# DDR4_SODIMM2.net
KiCad netlist of a schematic drawn in Altium Designer
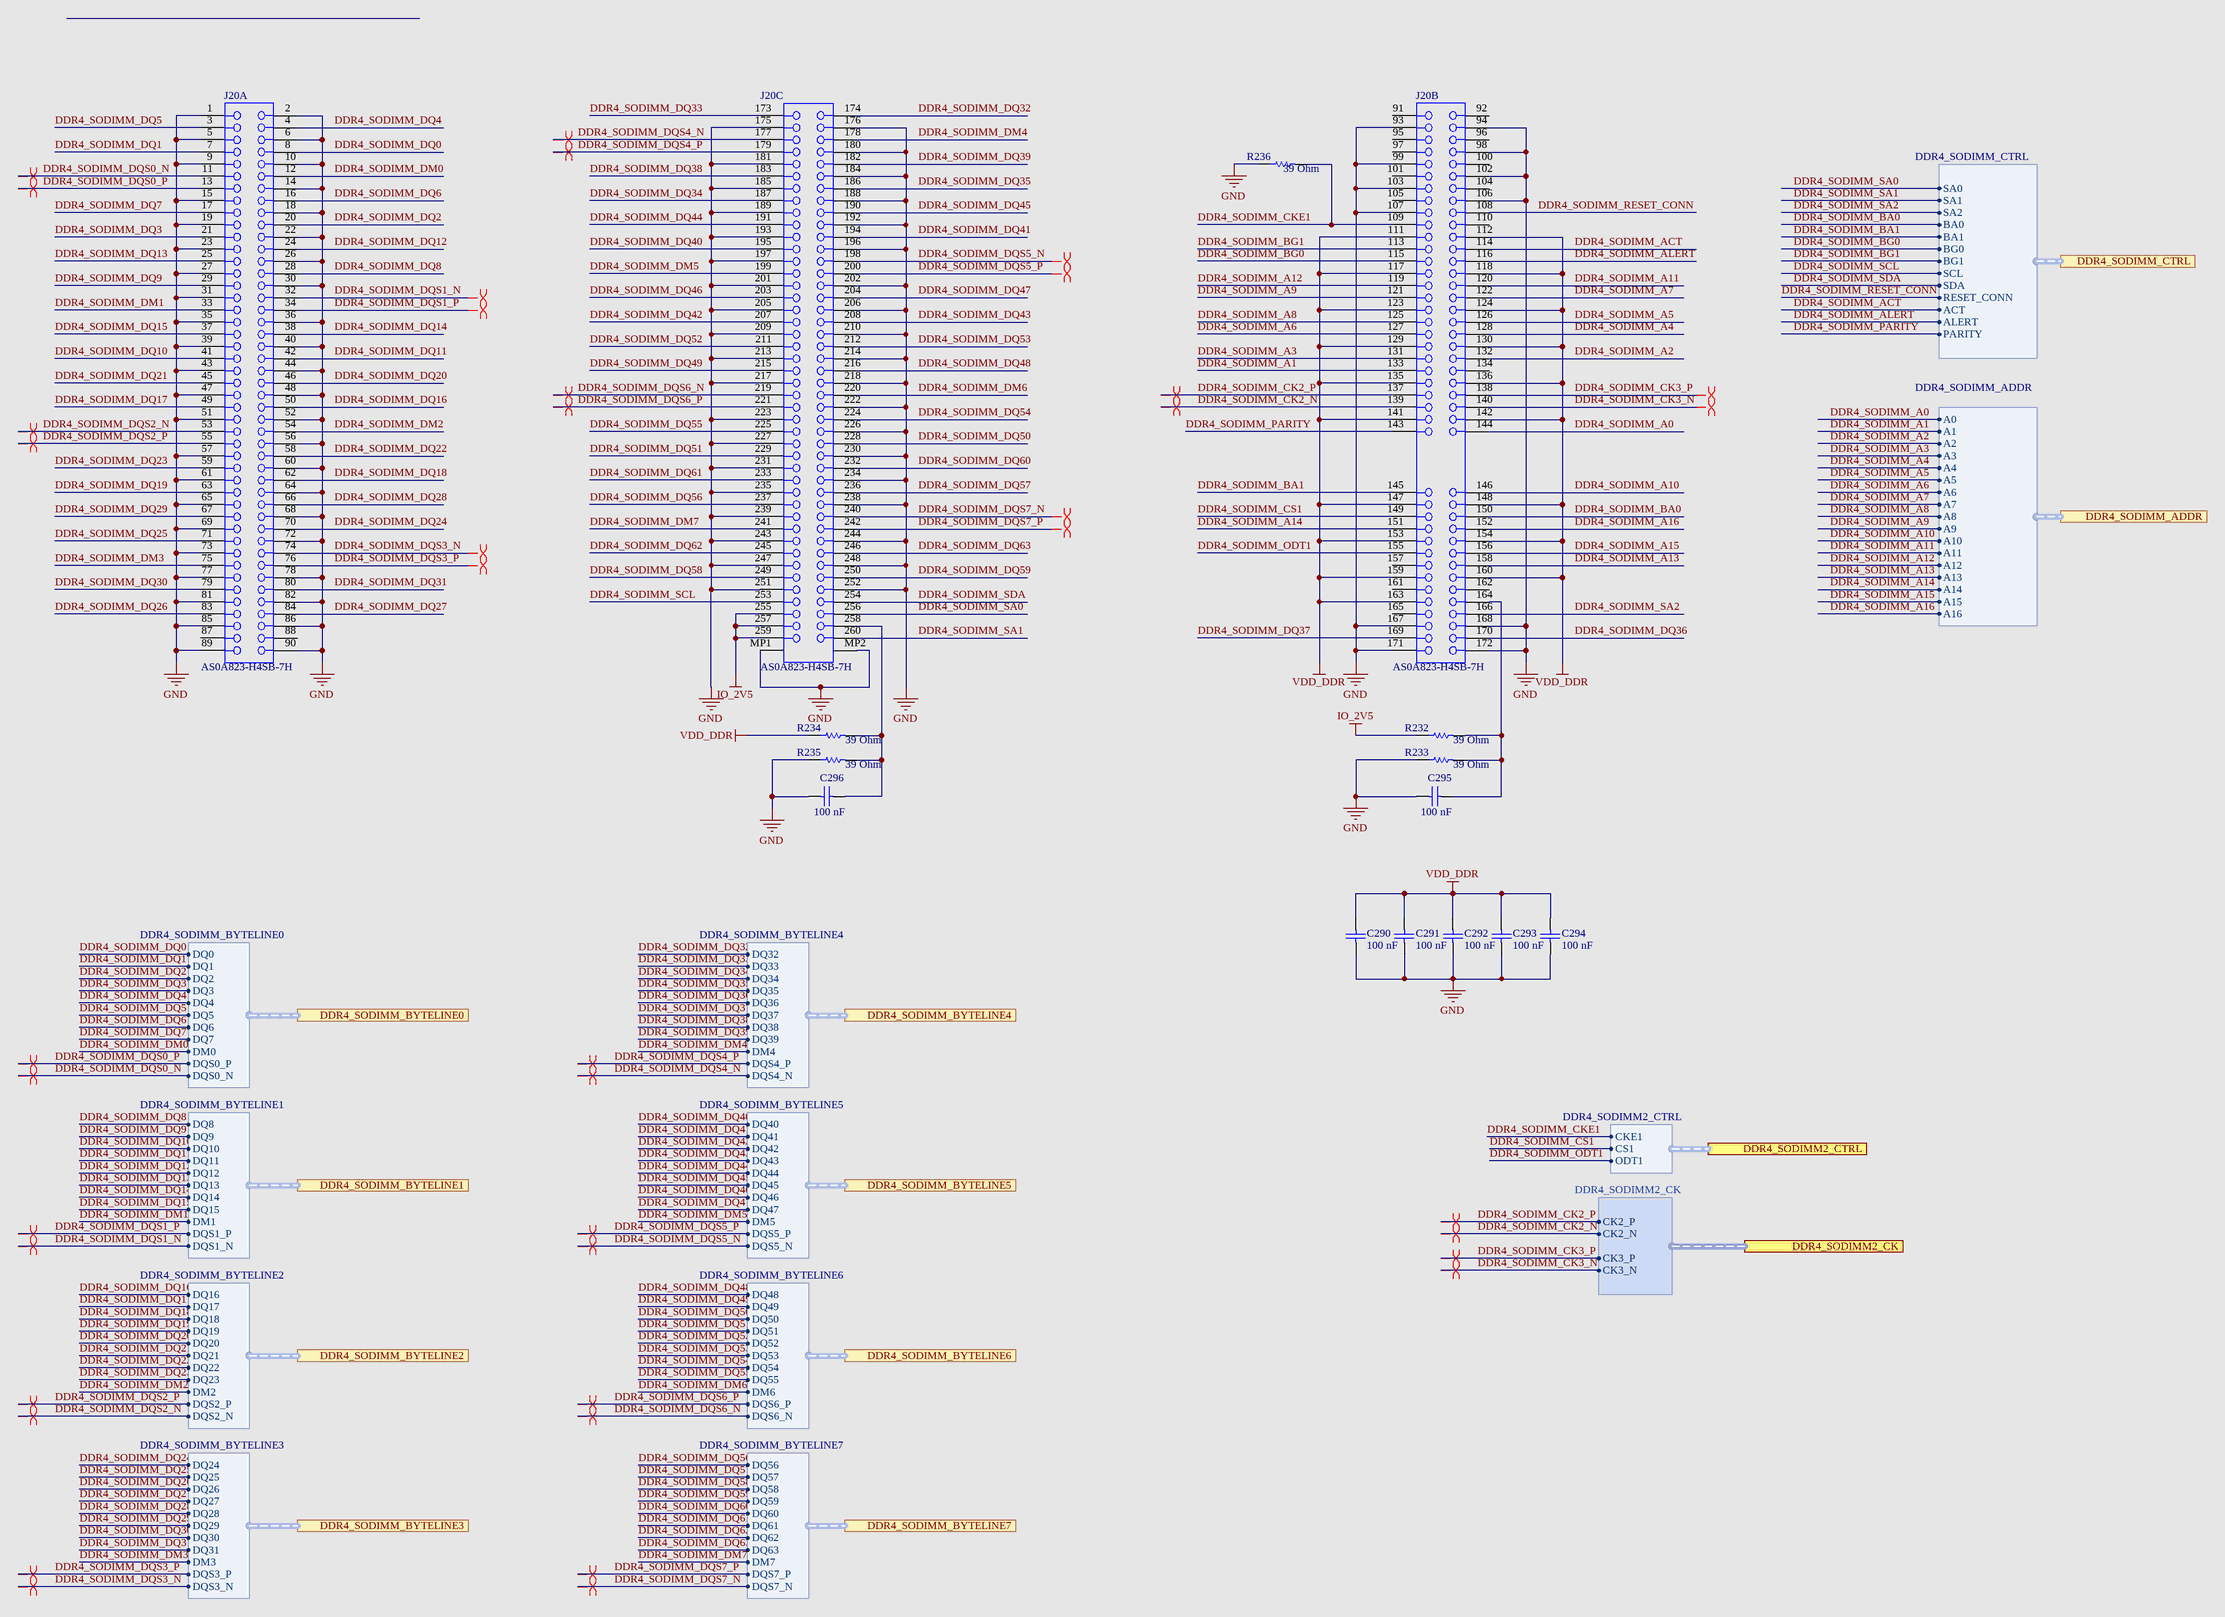
[diagram p0: DDR4_SODIMM2.SchDoc]

(export (version "E")
  (design (tool "Eeschema 10.0.6"))
  (components
    (comp (ref "C290")
      (value "C1005X7R1E104M")
      (footprint "CAPC1005X55X10LL05")
      (description "Chip Capacitor, 0.1 uF, +/- 20%, 25 V, -55 to 125 degC, 0402 (1005 Metric), RoHS, Tape and Reel")
      (fields (field (name "TOLERANCE") "20%") (field (name "CAPACITANCE") "100 nF"))
      (libsource (lib "Altium Content Vault") (part "CAP-NP-2"))
    )
    (comp (ref "C291")
      (value "C1005X7R1E104M")
      (footprint "CAPC1005X55X10LL05")
      (description "Chip Capacitor, 0.1 uF, +/- 20%, 25 V, -55 to 125 degC, 0402 (1005 Metric), RoHS, Tape and Reel")
      (fields (field (name "TOLERANCE") "20%") (field (name "CAPACITANCE") "100 nF"))
      (libsource (lib "Altium Content Vault") (part "CAP-NP-2"))
    )
    (comp (ref "C292")
      (value "C1005X7R1E104M")
      (footprint "CAPC1005X55X10LL05")
      (description "Chip Capacitor, 0.1 uF, +/- 20%, 25 V, -55 to 125 degC, 0402 (1005 Metric), RoHS, Tape and Reel")
      (fields (field (name "TOLERANCE") "20%") (field (name "CAPACITANCE") "100 nF"))
      (libsource (lib "Altium Content Vault") (part "CAP-NP-2"))
    )
    (comp (ref "C293")
      (value "C1005X7R1E104M")
      (footprint "CAPC1005X55X10LL05")
      (description "Chip Capacitor, 0.1 uF, +/- 20%, 25 V, -55 to 125 degC, 0402 (1005 Metric), RoHS, Tape and Reel")
      (fields (field (name "TOLERANCE") "20%") (field (name "CAPACITANCE") "100 nF"))
      (libsource (lib "Altium Content Vault") (part "CAP-NP-2"))
    )
    (comp (ref "C294")
      (value "C1005X7R1E104M")
      (footprint "CAPC1005X55X10LL05")
      (description "Chip Capacitor, 0.1 uF, +/- 20%, 25 V, -55 to 125 degC, 0402 (1005 Metric), RoHS, Tape and Reel")
      (fields (field (name "TOLERANCE") "20%") (field (name "CAPACITANCE") "100 nF"))
      (libsource (lib "Altium Content Vault") (part "CAP-NP-2"))
    )
    (comp (ref "C295")
      (value "C1005X7R1E104M")
      (footprint "CAPC1005X55X10LL05")
      (description "Chip Capacitor, 0.1 uF, +/- 20%, 25 V, -55 to 125 degC, 0402 (1005 Metric), RoHS, Tape and Reel")
      (fields (field (name "TOLERANCE") "20%") (field (name "CAPACITANCE") "100 nF"))
      (libsource (lib "Altium Content Vault") (part "CAP-NP-2"))
    )
    (comp (ref "C296")
      (value "C1005X7R1E104M")
      (footprint "CAPC1005X55X10LL05")
      (description "Chip Capacitor, 0.1 uF, +/- 20%, 25 V, -55 to 125 degC, 0402 (1005 Metric), RoHS, Tape and Reel")
      (fields (field (name "TOLERANCE") "20%") (field (name "CAPACITANCE") "100 nF"))
      (libsource (lib "Altium Content Vault") (part "CAP-NP-2"))
    )
    (comp (ref "J20")
      (value "AS0A823-H4SB-7H")
      (footprint "FOXC-AS0A823-H4SB-7H_V")
      (libsource (lib "Altium Content Vault") (part "CN-2S-2F-R260"))
    )
    (comp (ref "R232")
      (value "NRC04F49R9TRF")
      (footprint "RESC1005X35X25NL8T10")
      (description "Chip Resistor, 39 Ohm, +/- 5%, 0.063 W, -55 to 155 degC, 0402 (1005 Metric), RoHS, Tape and Reel")
      (fields
        (field (name "PARTNUMBER") "RC0402JR-0739RL")
        (field (name "TOLERANCE") "5%")
        (field (name "RESISTANCE") "39 Ohm")
      )
      (libsource (lib "Altium Content Vault") (part "CMP-2002-07994-2"))
    )
    (comp (ref "R233")
      (value "NRC04F49R9TRF")
      (footprint "RESC1005X35X25NL8T10")
      (description "Chip Resistor, 39 Ohm, +/- 5%, 0.063 W, -55 to 155 degC, 0402 (1005 Metric), RoHS, Tape and Reel")
      (fields
        (field (name "PARTNUMBER") "RC0402JR-0739RL")
        (field (name "TOLERANCE") "5%")
        (field (name "RESISTANCE") "39 Ohm")
      )
      (libsource (lib "Altium Content Vault") (part "CMP-2002-07994-2"))
    )
    (comp (ref "R234")
      (value "NRC04F49R9TRF")
      (footprint "RESC1005X35X25NL8T10")
      (description "Chip Resistor, 39 Ohm, +/- 5%, 0.063 W, -55 to 155 degC, 0402 (1005 Metric), RoHS, Tape and Reel")
      (fields
        (field (name "PARTNUMBER") "RC0402JR-0739RL")
        (field (name "TOLERANCE") "5%")
        (field (name "RESISTANCE") "39 Ohm")
      )
      (libsource (lib "Altium Content Vault") (part "CMP-2002-07994-2"))
    )
    (comp (ref "R235")
      (value "NRC04F49R9TRF")
      (footprint "RESC1005X35X25NL8T10")
      (description "Chip Resistor, 39 Ohm, +/- 5%, 0.063 W, -55 to 155 degC, 0402 (1005 Metric), RoHS, Tape and Reel")
      (fields
        (field (name "PARTNUMBER") "RC0402JR-0739RL")
        (field (name "TOLERANCE") "5%")
        (field (name "RESISTANCE") "39 Ohm")
      )
      (libsource (lib "Altium Content Vault") (part "CMP-2002-07994-2"))
    )
    (comp (ref "R236")
      (value "RC0402JR-0739RL")
      (footprint "RESC1005X40X25NL5T10")
      (description "Chip Resistor, 39 Ohm, +/- 5%, 0.063 W, -55 to 155 degC, 0402 (1005 Metric), RoHS, Tape and Reel")
      (fields (field (name "TOLERANCE") "5%") (field (name "RESISTANCE") "39 Ohm"))
      (libsource (lib "Altium Content Vault") (part "CMP-2002-07994-2"))
    )
  )
  (nets
    (net (code "13") (name "/DDR4_SODIMM_A0") (class "Default")
      (node (ref "J20") (pin "144") (pinfunction "144_144") (pintype "passive"))
    )
    (net (code "14") (name "/DDR4_SODIMM_A1") (class "Default")
      (node (ref "J20") (pin "133") (pinfunction "133_133") (pintype "passive"))
    )
    (net (code "15") (name "/DDR4_SODIMM_A2") (class "Default")
      (node (ref "J20") (pin "132") (pinfunction "132_132") (pintype "passive"))
    )
    (net (code "16") (name "/DDR4_SODIMM_A3") (class "Default")
      (node (ref "J20") (pin "131") (pinfunction "131_131") (pintype "passive"))
    )
    (net (code "17") (name "/DDR4_SODIMM_A4") (class "Default")
      (node (ref "J20") (pin "128") (pinfunction "128_128") (pintype "passive"))
    )
    (net (code "18") (name "/DDR4_SODIMM_A5") (class "Default")
      (node (ref "J20") (pin "126") (pinfunction "126_126") (pintype "passive"))
    )
    (net (code "19") (name "/DDR4_SODIMM_A6") (class "Default")
      (node (ref "J20") (pin "127") (pinfunction "127_127") (pintype "passive"))
    )
    (net (code "20") (name "/DDR4_SODIMM_A7") (class "Default")
      (node (ref "J20") (pin "122") (pinfunction "122_122") (pintype "passive"))
    )
    (net (code "21") (name "/DDR4_SODIMM_A8") (class "Default")
      (node (ref "J20") (pin "125") (pinfunction "125_125") (pintype "passive"))
    )
    (net (code "22") (name "/DDR4_SODIMM_A9") (class "Default")
      (node (ref "J20") (pin "121") (pinfunction "121_121") (pintype "passive"))
    )
    (net (code "23") (name "/DDR4_SODIMM_A10") (class "Default")
      (node (ref "J20") (pin "146") (pinfunction "146_146") (pintype "passive"))
    )
    (net (code "24") (name "/DDR4_SODIMM_A11") (class "Default")
      (node (ref "J20") (pin "120") (pinfunction "120_120") (pintype "passive"))
    )
    (net (code "25") (name "/DDR4_SODIMM_A12") (class "Default")
      (node (ref "J20") (pin "119") (pinfunction "119_119") (pintype "passive"))
    )
    (net (code "26") (name "/DDR4_SODIMM_A13") (class "Default")
      (node (ref "J20") (pin "158") (pinfunction "158_158") (pintype "passive"))
    )
    (net (code "27") (name "/DDR4_SODIMM_A14") (class "Default")
      (node (ref "J20") (pin "151") (pinfunction "151_151") (pintype "passive"))
    )
    (net (code "28") (name "/DDR4_SODIMM_A15") (class "Default")
      (node (ref "J20") (pin "156") (pinfunction "156_156") (pintype "passive"))
    )
    (net (code "29") (name "/DDR4_SODIMM_A16") (class "Default")
      (node (ref "J20") (pin "152") (pinfunction "152_152") (pintype "passive"))
    )
    (net (code "30") (name "/DDR4_SODIMM_ACT") (class "Default")
      (node (ref "J20") (pin "114") (pinfunction "114_114") (pintype "passive"))
    )
    (net (code "31") (name "/DDR4_SODIMM_ALERT") (class "Default")
      (node (ref "J20") (pin "116") (pinfunction "116_116") (pintype "passive"))
    )
    (net (code "32") (name "/DDR4_SODIMM_BA0") (class "Default")
      (node (ref "J20") (pin "150") (pinfunction "150_150") (pintype "passive"))
    )
    (net (code "33") (name "/DDR4_SODIMM_BA1") (class "Default")
      (node (ref "J20") (pin "145") (pinfunction "145_145") (pintype "passive"))
    )
    (net (code "34") (name "/DDR4_SODIMM_BG0") (class "Default")
      (node (ref "J20") (pin "115") (pinfunction "115_115") (pintype "passive"))
    )
    (net (code "35") (name "/DDR4_SODIMM_BG1") (class "Default")
      (node (ref "J20") (pin "113") (pinfunction "113_113") (pintype "passive"))
    )
    (net (code "36") (name "/DDR4_SODIMM_CK2_N") (class "Default")
      (node (ref "J20") (pin "139") (pinfunction "139_139") (pintype "passive"))
    )
    (net (code "37") (name "/DDR4_SODIMM_CK2_P") (class "Default")
      (node (ref "J20") (pin "137") (pinfunction "137_137") (pintype "passive"))
    )
    (net (code "38") (name "/DDR4_SODIMM_CK3_N") (class "Default")
      (node (ref "J20") (pin "140") (pinfunction "140_140") (pintype "passive"))
    )
    (net (code "39") (name "/DDR4_SODIMM_CK3_P") (class "Default")
      (node (ref "J20") (pin "138") (pinfunction "138_138") (pintype "passive"))
    )
    (net (code "40") (name "/DDR4_SODIMM_CKE1") (class "Default")
      (node (ref "J20") (pin "109") (pinfunction "109_109") (pintype "passive"))
      (node (ref "R236") (pin "2") (pinfunction "2_2") (pintype "passive"))
    )
    (net (code "41") (name "/DDR4_SODIMM_CS1") (class "Default")
      (node (ref "J20") (pin "149") (pinfunction "149_149") (pintype "passive"))
    )
    (net (code "42") (name "/DDR4_SODIMM_DM0") (class "Default")
      (node (ref "J20") (pin "12") (pinfunction "12_12") (pintype "passive"))
    )
    (net (code "43") (name "/DDR4_SODIMM_DM1") (class "Default")
      (node (ref "J20") (pin "33") (pinfunction "33_33") (pintype "passive"))
    )
    (net (code "44") (name "/DDR4_SODIMM_DM2") (class "Default")
      (node (ref "J20") (pin "54") (pinfunction "54_54") (pintype "passive"))
    )
    (net (code "45") (name "/DDR4_SODIMM_DM3") (class "Default")
      (node (ref "J20") (pin "75") (pinfunction "75_75") (pintype "passive"))
    )
    (net (code "46") (name "/DDR4_SODIMM_DM4") (class "Default")
      (node (ref "J20") (pin "178") (pinfunction "178_178") (pintype "passive"))
    )
    (net (code "47") (name "/DDR4_SODIMM_DM5") (class "Default")
      (node (ref "J20") (pin "199") (pinfunction "199_199") (pintype "passive"))
    )
    (net (code "48") (name "/DDR4_SODIMM_DM6") (class "Default")
      (node (ref "J20") (pin "220") (pinfunction "220_220") (pintype "passive"))
    )
    (net (code "49") (name "/DDR4_SODIMM_DM7") (class "Default")
      (node (ref "J20") (pin "241") (pinfunction "241_241") (pintype "passive"))
    )
    (net (code "50") (name "/DDR4_SODIMM_DQ0") (class "Default")
      (node (ref "J20") (pin "8") (pinfunction "8_8") (pintype "passive"))
    )
    (net (code "51") (name "/DDR4_SODIMM_DQ1") (class "Default")
      (node (ref "J20") (pin "7") (pinfunction "7_7") (pintype "passive"))
    )
    (net (code "52") (name "/DDR4_SODIMM_DQ2") (class "Default")
      (node (ref "J20") (pin "20") (pinfunction "20_20") (pintype "passive"))
    )
    (net (code "53") (name "/DDR4_SODIMM_DQ3") (class "Default")
      (node (ref "J20") (pin "21") (pinfunction "21_21") (pintype "passive"))
    )
    (net (code "54") (name "/DDR4_SODIMM_DQ4") (class "Default")
      (node (ref "J20") (pin "4") (pinfunction "4_4") (pintype "passive"))
    )
    (net (code "55") (name "/DDR4_SODIMM_DQ5") (class "Default")
      (node (ref "J20") (pin "3") (pinfunction "3_3") (pintype "passive"))
    )
    (net (code "56") (name "/DDR4_SODIMM_DQ6") (class "Default")
      (node (ref "J20") (pin "16") (pinfunction "16_16") (pintype "passive"))
    )
    (net (code "57") (name "/DDR4_SODIMM_DQ7") (class "Default")
      (node (ref "J20") (pin "17") (pinfunction "17_17") (pintype "passive"))
    )
    (net (code "58") (name "/DDR4_SODIMM_DQ8") (class "Default")
      (node (ref "J20") (pin "28") (pinfunction "28_28") (pintype "passive"))
    )
    (net (code "59") (name "/DDR4_SODIMM_DQ9") (class "Default")
      (node (ref "J20") (pin "29") (pinfunction "29_29") (pintype "passive"))
    )
    (net (code "60") (name "/DDR4_SODIMM_DQ10") (class "Default")
      (node (ref "J20") (pin "41") (pinfunction "41_41") (pintype "passive"))
    )
    (net (code "61") (name "/DDR4_SODIMM_DQ11") (class "Default")
      (node (ref "J20") (pin "42") (pinfunction "42_42") (pintype "passive"))
    )
    (net (code "62") (name "/DDR4_SODIMM_DQ12") (class "Default")
      (node (ref "J20") (pin "24") (pinfunction "24_24") (pintype "passive"))
    )
    (net (code "63") (name "/DDR4_SODIMM_DQ13") (class "Default")
      (node (ref "J20") (pin "25") (pinfunction "25_25") (pintype "passive"))
    )
    (net (code "64") (name "/DDR4_SODIMM_DQ14") (class "Default")
      (node (ref "J20") (pin "38") (pinfunction "38_38") (pintype "passive"))
    )
    (net (code "65") (name "/DDR4_SODIMM_DQ15") (class "Default")
      (node (ref "J20") (pin "37") (pinfunction "37_37") (pintype "passive"))
    )
    (net (code "66") (name "/DDR4_SODIMM_DQ16") (class "Default")
      (node (ref "J20") (pin "50") (pinfunction "50_50") (pintype "passive"))
    )
    (net (code "67") (name "/DDR4_SODIMM_DQ17") (class "Default")
      (node (ref "J20") (pin "49") (pinfunction "49_49") (pintype "passive"))
    )
    (net (code "68") (name "/DDR4_SODIMM_DQ18") (class "Default")
      (node (ref "J20") (pin "62") (pinfunction "62_62") (pintype "passive"))
    )
    (net (code "69") (name "/DDR4_SODIMM_DQ19") (class "Default")
      (node (ref "J20") (pin "63") (pinfunction "63_63") (pintype "passive"))
    )
    (net (code "70") (name "/DDR4_SODIMM_DQ20") (class "Default")
      (node (ref "J20") (pin "46") (pinfunction "46_46") (pintype "passive"))
    )
    (net (code "71") (name "/DDR4_SODIMM_DQ21") (class "Default")
      (node (ref "J20") (pin "45") (pinfunction "45_45") (pintype "passive"))
    )
    (net (code "72") (name "/DDR4_SODIMM_DQ22") (class "Default")
      (node (ref "J20") (pin "58") (pinfunction "58_58") (pintype "passive"))
    )
    (net (code "73") (name "/DDR4_SODIMM_DQ23") (class "Default")
      (node (ref "J20") (pin "59") (pinfunction "59_59") (pintype "passive"))
    )
    (net (code "74") (name "/DDR4_SODIMM_DQ24") (class "Default")
      (node (ref "J20") (pin "70") (pinfunction "70_70") (pintype "passive"))
    )
    (net (code "75") (name "/DDR4_SODIMM_DQ25") (class "Default")
      (node (ref "J20") (pin "71") (pinfunction "71_71") (pintype "passive"))
    )
    (net (code "76") (name "/DDR4_SODIMM_DQ26") (class "Default")
      (node (ref "J20") (pin "83") (pinfunction "83_83") (pintype "passive"))
    )
    (net (code "77") (name "/DDR4_SODIMM_DQ27") (class "Default")
      (node (ref "J20") (pin "84") (pinfunction "84_84") (pintype "passive"))
    )
    (net (code "78") (name "/DDR4_SODIMM_DQ28") (class "Default")
      (node (ref "J20") (pin "66") (pinfunction "66_66") (pintype "passive"))
    )
    (net (code "79") (name "/DDR4_SODIMM_DQ29") (class "Default")
      (node (ref "J20") (pin "67") (pinfunction "67_67") (pintype "passive"))
    )
    (net (code "80") (name "/DDR4_SODIMM_DQ30") (class "Default")
      (node (ref "J20") (pin "79") (pinfunction "79_79") (pintype "passive"))
    )
    (net (code "81") (name "/DDR4_SODIMM_DQ31") (class "Default")
      (node (ref "J20") (pin "80") (pinfunction "80_80") (pintype "passive"))
    )
    (net (code "82") (name "/DDR4_SODIMM_DQ32") (class "Default")
      (node (ref "J20") (pin "174") (pinfunction "174_174") (pintype "passive"))
    )
    (net (code "83") (name "/DDR4_SODIMM_DQ33") (class "Default")
      (node (ref "J20") (pin "173") (pinfunction "173_173") (pintype "passive"))
    )
    (net (code "84") (name "/DDR4_SODIMM_DQ34") (class "Default")
      (node (ref "J20") (pin "187") (pinfunction "187_187") (pintype "passive"))
    )
    (net (code "85") (name "/DDR4_SODIMM_DQ35") (class "Default")
      (node (ref "J20") (pin "186") (pinfunction "186_186") (pintype "passive"))
    )
    (net (code "86") (name "/DDR4_SODIMM_DQ36") (class "Default")
      (node (ref "J20") (pin "170") (pinfunction "170_170") (pintype "passive"))
    )
    (net (code "87") (name "/DDR4_SODIMM_DQ37") (class "Default")
      (node (ref "J20") (pin "169") (pinfunction "169_169") (pintype "passive"))
    )
    (net (code "88") (name "/DDR4_SODIMM_DQ38") (class "Default")
      (node (ref "J20") (pin "183") (pinfunction "183_183") (pintype "passive"))
    )
    (net (code "89") (name "/DDR4_SODIMM_DQ39") (class "Default")
      (node (ref "J20") (pin "182") (pinfunction "182_182") (pintype "passive"))
    )
    (net (code "90") (name "/DDR4_SODIMM_DQ40") (class "Default")
      (node (ref "J20") (pin "195") (pinfunction "195_195") (pintype "passive"))
    )
    (net (code "91") (name "/DDR4_SODIMM_DQ41") (class "Default")
      (node (ref "J20") (pin "194") (pinfunction "194_194") (pintype "passive"))
    )
    (net (code "92") (name "/DDR4_SODIMM_DQ42") (class "Default")
      (node (ref "J20") (pin "207") (pinfunction "207_207") (pintype "passive"))
    )
    (net (code "93") (name "/DDR4_SODIMM_DQ43") (class "Default")
      (node (ref "J20") (pin "208") (pinfunction "208_208") (pintype "passive"))
    )
    (net (code "94") (name "/DDR4_SODIMM_DQ44") (class "Default")
      (node (ref "J20") (pin "191") (pinfunction "191_191") (pintype "passive"))
    )
    (net (code "95") (name "/DDR4_SODIMM_DQ45") (class "Default")
      (node (ref "J20") (pin "190") (pinfunction "190_190") (pintype "passive"))
    )
    (net (code "96") (name "/DDR4_SODIMM_DQ46") (class "Default")
      (node (ref "J20") (pin "203") (pinfunction "203_203") (pintype "passive"))
    )
    (net (code "97") (name "/DDR4_SODIMM_DQ47") (class "Default")
      (node (ref "J20") (pin "204") (pinfunction "204_204") (pintype "passive"))
    )
    (net (code "98") (name "/DDR4_SODIMM_DQ48") (class "Default")
      (node (ref "J20") (pin "216") (pinfunction "216_216") (pintype "passive"))
    )
    (net (code "99") (name "/DDR4_SODIMM_DQ49") (class "Default")
      (node (ref "J20") (pin "215") (pinfunction "215_215") (pintype "passive"))
    )
    (net (code "100") (name "/DDR4_SODIMM_DQ50") (class "Default")
      (node (ref "J20") (pin "228") (pinfunction "228_228") (pintype "passive"))
    )
    (net (code "101") (name "/DDR4_SODIMM_DQ51") (class "Default")
      (node (ref "J20") (pin "229") (pinfunction "229_229") (pintype "passive"))
    )
    (net (code "102") (name "/DDR4_SODIMM_DQ52") (class "Default")
      (node (ref "J20") (pin "211") (pinfunction "211_211") (pintype "passive"))
    )
    (net (code "103") (name "/DDR4_SODIMM_DQ53") (class "Default")
      (node (ref "J20") (pin "212") (pinfunction "212_212") (pintype "passive"))
    )
    (net (code "104") (name "/DDR4_SODIMM_DQ54") (class "Default")
      (node (ref "J20") (pin "224") (pinfunction "224_224") (pintype "passive"))
    )
    (net (code "105") (name "/DDR4_SODIMM_DQ55") (class "Default")
      (node (ref "J20") (pin "225") (pinfunction "225_225") (pintype "passive"))
    )
    (net (code "106") (name "/DDR4_SODIMM_DQ56") (class "Default")
      (node (ref "J20") (pin "237") (pinfunction "237_237") (pintype "passive"))
    )
    (net (code "107") (name "/DDR4_SODIMM_DQ57") (class "Default")
      (node (ref "J20") (pin "236") (pinfunction "236_236") (pintype "passive"))
    )
    (net (code "108") (name "/DDR4_SODIMM_DQ58") (class "Default")
      (node (ref "J20") (pin "249") (pinfunction "249_249") (pintype "passive"))
    )
    (net (code "109") (name "/DDR4_SODIMM_DQ59") (class "Default")
      (node (ref "J20") (pin "250") (pinfunction "250_250") (pintype "passive"))
    )
    (net (code "110") (name "/DDR4_SODIMM_DQ60") (class "Default")
      (node (ref "J20") (pin "232") (pinfunction "232_232") (pintype "passive"))
    )
    (net (code "111") (name "/DDR4_SODIMM_DQ61") (class "Default")
      (node (ref "J20") (pin "233") (pinfunction "233_233") (pintype "passive"))
    )
    (net (code "112") (name "/DDR4_SODIMM_DQ62") (class "Default")
      (node (ref "J20") (pin "245") (pinfunction "245_245") (pintype "passive"))
    )
    (net (code "113") (name "/DDR4_SODIMM_DQ63") (class "Default")
      (node (ref "J20") (pin "246") (pinfunction "246_246") (pintype "passive"))
    )
    (net (code "114") (name "/DDR4_SODIMM_DQS0_N") (class "Default")
      (node (ref "J20") (pin "11") (pinfunction "11_11") (pintype "passive"))
    )
    (net (code "115") (name "/DDR4_SODIMM_DQS0_P") (class "Default")
      (node (ref "J20") (pin "13") (pinfunction "13_13") (pintype "passive"))
    )
    (net (code "116") (name "/DDR4_SODIMM_DQS1_N") (class "Default")
      (node (ref "J20") (pin "32") (pinfunction "32_32") (pintype "passive"))
    )
    (net (code "117") (name "/DDR4_SODIMM_DQS1_P") (class "Default")
      (node (ref "J20") (pin "34") (pinfunction "34_34") (pintype "passive"))
    )
    (net (code "118") (name "/DDR4_SODIMM_DQS2_N") (class "Default")
      (node (ref "J20") (pin "53") (pinfunction "53_53") (pintype "passive"))
    )
    (net (code "119") (name "/DDR4_SODIMM_DQS2_P") (class "Default")
      (node (ref "J20") (pin "55") (pinfunction "55_55") (pintype "passive"))
    )
    (net (code "120") (name "/DDR4_SODIMM_DQS3_N") (class "Default")
      (node (ref "J20") (pin "74") (pinfunction "74_74") (pintype "passive"))
    )
    (net (code "121") (name "/DDR4_SODIMM_DQS3_P") (class "Default")
      (node (ref "J20") (pin "76") (pinfunction "76_76") (pintype "passive"))
    )
    (net (code "122") (name "/DDR4_SODIMM_DQS4_N") (class "Default")
      (node (ref "J20") (pin "177") (pinfunction "177_177") (pintype "passive"))
    )
    (net (code "123") (name "/DDR4_SODIMM_DQS4_P") (class "Default")
      (node (ref "J20") (pin "179") (pinfunction "179_179") (pintype "passive"))
    )
    (net (code "124") (name "/DDR4_SODIMM_DQS5_N") (class "Default")
      (node (ref "J20") (pin "198") (pinfunction "198_198") (pintype "passive"))
    )
    (net (code "125") (name "/DDR4_SODIMM_DQS5_P") (class "Default")
      (node (ref "J20") (pin "200") (pinfunction "200_200") (pintype "passive"))
    )
    (net (code "126") (name "/DDR4_SODIMM_DQS6_N") (class "Default")
      (node (ref "J20") (pin "219") (pinfunction "219_219") (pintype "passive"))
    )
    (net (code "127") (name "/DDR4_SODIMM_DQS6_P") (class "Default")
      (node (ref "J20") (pin "221") (pinfunction "221_221") (pintype "passive"))
    )
    (net (code "128") (name "/DDR4_SODIMM_DQS7_N") (class "Default")
      (node (ref "J20") (pin "240") (pinfunction "240_240") (pintype "passive"))
    )
    (net (code "129") (name "/DDR4_SODIMM_DQS7_P") (class "Default")
      (node (ref "J20") (pin "242") (pinfunction "242_242") (pintype "passive"))
    )
    (net (code "130") (name "/DDR4_SODIMM_ODT1") (class "Default")
      (node (ref "J20") (pin "155") (pinfunction "155_155") (pintype "passive"))
    )
    (net (code "131") (name "/DDR4_SODIMM_PARITY") (class "Default")
      (node (ref "J20") (pin "143") (pinfunction "143_143") (pintype "passive"))
    )
    (net (code "132") (name "/DDR4_SODIMM_RESET_CONN") (class "Default")
      (node (ref "J20") (pin "108") (pinfunction "108_108") (pintype "passive"))
    )
    (net (code "133") (name "/DDR4_SODIMM_SA0") (class "Default")
      (node (ref "J20") (pin "256") (pinfunction "256_256") (pintype "passive"))
    )
    (net (code "134") (name "/DDR4_SODIMM_SA1") (class "Default")
      (node (ref "J20") (pin "260") (pinfunction "260_260") (pintype "passive"))
    )
    (net (code "135") (name "/DDR4_SODIMM_SA2") (class "Default")
      (node (ref "J20") (pin "166") (pinfunction "166_166") (pintype "passive"))
    )
    (net (code "136") (name "/DDR4_SODIMM_SCL") (class "Default")
      (node (ref "J20") (pin "253") (pinfunction "253_253") (pintype "passive"))
    )
    (net (code "137") (name "/DDR4_SODIMM_SDA") (class "Default")
      (node (ref "J20") (pin "254") (pinfunction "254_254") (pintype "passive"))
    )
    (net (code "150") (name "GND") (class "Default")
      (node (ref "C290") (pin "2") (pinfunction "2_2") (pintype "passive"))
      (node (ref "C291") (pin "2") (pinfunction "2_2") (pintype "passive"))
      (node (ref "C292") (pin "2") (pinfunction "2_2") (pintype "passive"))
      (node (ref "C293") (pin "2") (pinfunction "2_2") (pintype "passive"))
      (node (ref "C294") (pin "2") (pinfunction "2_2") (pintype "passive"))
      (node (ref "C295") (pin "2") (pinfunction "2_2") (pintype "passive"))
      (node (ref "C296") (pin "2") (pinfunction "2_2") (pintype "passive"))
      (node (ref "J20") (pin "1") (pinfunction "1_1") (pintype "passive"))
      (node (ref "J20") (pin "10") (pinfunction "10_10") (pintype "passive"))
      (node (ref "J20") (pin "102") (pinfunction "102_102") (pintype "passive"))
      (node (ref "J20") (pin "103") (pinfunction "103_103") (pintype "passive"))
      (node (ref "J20") (pin "106") (pinfunction "106_106") (pintype "passive"))
      (node (ref "J20") (pin "107") (pinfunction "107_107") (pintype "passive"))
      (node (ref "J20") (pin "14") (pinfunction "14_14") (pintype "passive"))
      (node (ref "J20") (pin "15") (pinfunction "15_15") (pintype "passive"))
      (node (ref "J20") (pin "167") (pinfunction "167_167") (pintype "passive"))
      (node (ref "J20") (pin "168") (pinfunction "168_168") (pintype "passive"))
      (node (ref "J20") (pin "171") (pinfunction "171_171") (pintype "passive"))
      (node (ref "J20") (pin "172") (pinfunction "172_172") (pintype "passive"))
      (node (ref "J20") (pin "175") (pinfunction "175_175") (pintype "passive"))
      (node (ref "J20") (pin "176") (pinfunction "176_176") (pintype "passive"))
      (node (ref "J20") (pin "18") (pinfunction "18_18") (pintype "passive"))
      (node (ref "J20") (pin "180") (pinfunction "180_180") (pintype "passive"))
      (node (ref "J20") (pin "181") (pinfunction "181_181") (pintype "passive"))
      (node (ref "J20") (pin "184") (pinfunction "184_184") (pintype "passive"))
      (node (ref "J20") (pin "185") (pinfunction "185_185") (pintype "passive"))
      (node (ref "J20") (pin "188") (pinfunction "188_188") (pintype "passive"))
      (node (ref "J20") (pin "189") (pinfunction "189_189") (pintype "passive"))
      (node (ref "J20") (pin "19") (pinfunction "19_19") (pintype "passive"))
      (node (ref "J20") (pin "192") (pinfunction "192_192") (pintype "passive"))
      (node (ref "J20") (pin "193") (pinfunction "193_193") (pintype "passive"))
      (node (ref "J20") (pin "196") (pinfunction "196_196") (pintype "passive"))
      (node (ref "J20") (pin "197") (pinfunction "197_197") (pintype "passive"))
      (node (ref "J20") (pin "2") (pinfunction "2_2") (pintype "passive"))
      (node (ref "J20") (pin "201") (pinfunction "201_201") (pintype "passive"))
      (node (ref "J20") (pin "202") (pinfunction "202_202") (pintype "passive"))
      (node (ref "J20") (pin "205") (pinfunction "205_205") (pintype "passive"))
      (node (ref "J20") (pin "206") (pinfunction "206_206") (pintype "passive"))
      (node (ref "J20") (pin "209") (pinfunction "209_209") (pintype "passive"))
      (node (ref "J20") (pin "210") (pinfunction "210_210") (pintype "passive"))
      (node (ref "J20") (pin "213") (pinfunction "213_213") (pintype "passive"))
      (node (ref "J20") (pin "214") (pinfunction "214_214") (pintype "passive"))
      (node (ref "J20") (pin "217") (pinfunction "217_217") (pintype "passive"))
      (node (ref "J20") (pin "218") (pinfunction "218_218") (pintype "passive"))
      (node (ref "J20") (pin "22") (pinfunction "22_22") (pintype "passive"))
      (node (ref "J20") (pin "222") (pinfunction "222_222") (pintype "passive"))
      (node (ref "J20") (pin "223") (pinfunction "223_223") (pintype "passive"))
      (node (ref "J20") (pin "226") (pinfunction "226_226") (pintype "passive"))
      (node (ref "J20") (pin "227") (pinfunction "227_227") (pintype "passive"))
      (node (ref "J20") (pin "23") (pinfunction "23_23") (pintype "passive"))
      (node (ref "J20") (pin "230") (pinfunction "230_230") (pintype "passive"))
      (node (ref "J20") (pin "231") (pinfunction "231_231") (pintype "passive"))
      (node (ref "J20") (pin "234") (pinfunction "234_234") (pintype "passive"))
      (node (ref "J20") (pin "235") (pinfunction "235_235") (pintype "passive"))
      (node (ref "J20") (pin "238") (pinfunction "238_238") (pintype "passive"))
      (node (ref "J20") (pin "239") (pinfunction "239_239") (pintype "passive"))
      (node (ref "J20") (pin "243") (pinfunction "243_243") (pintype "passive"))
      (node (ref "J20") (pin "244") (pinfunction "244_244") (pintype "passive"))
      (node (ref "J20") (pin "247") (pinfunction "247_247") (pintype "passive"))
      (node (ref "J20") (pin "248") (pinfunction "248_248") (pintype "passive"))
      (node (ref "J20") (pin "251") (pinfunction "251_251") (pintype "passive"))
      (node (ref "J20") (pin "252") (pinfunction "252_252") (pintype "passive"))
      (node (ref "J20") (pin "26") (pinfunction "26_26") (pintype "passive"))
      (node (ref "J20") (pin "27") (pinfunction "27_27") (pintype "passive"))
      (node (ref "J20") (pin "30") (pinfunction "30_30") (pintype "passive"))
      (node (ref "J20") (pin "31") (pinfunction "31_31") (pintype "passive"))
      (node (ref "J20") (pin "35") (pinfunction "35_35") (pintype "passive"))
      (node (ref "J20") (pin "36") (pinfunction "36_36") (pintype "passive"))
      (node (ref "J20") (pin "39") (pinfunction "39_39") (pintype "passive"))
      (node (ref "J20") (pin "40") (pinfunction "40_40") (pintype "passive"))
      (node (ref "J20") (pin "43") (pinfunction "43_43") (pintype "passive"))
      (node (ref "J20") (pin "44") (pinfunction "44_44") (pintype "passive"))
      (node (ref "J20") (pin "47") (pinfunction "47_47") (pintype "passive"))
      (node (ref "J20") (pin "48") (pinfunction "48_48") (pintype "passive"))
      (node (ref "J20") (pin "5") (pinfunction "5_5") (pintype "passive"))
      (node (ref "J20") (pin "51") (pinfunction "51_51") (pintype "passive"))
      (node (ref "J20") (pin "52") (pinfunction "52_52") (pintype "passive"))
      (node (ref "J20") (pin "56") (pinfunction "56_56") (pintype "passive"))
      (node (ref "J20") (pin "57") (pinfunction "57_57") (pintype "passive"))
      (node (ref "J20") (pin "6") (pinfunction "6_6") (pintype "passive"))
      (node (ref "J20") (pin "60") (pinfunction "60_60") (pintype "passive"))
      (node (ref "J20") (pin "61") (pinfunction "61_61") (pintype "passive"))
      (node (ref "J20") (pin "64") (pinfunction "64_64") (pintype "passive"))
      (node (ref "J20") (pin "65") (pinfunction "65_65") (pintype "passive"))
      (node (ref "J20") (pin "68") (pinfunction "68_68") (pintype "passive"))
      (node (ref "J20") (pin "69") (pinfunction "69_69") (pintype "passive"))
      (node (ref "J20") (pin "72") (pinfunction "72_72") (pintype "passive"))
      (node (ref "J20") (pin "73") (pinfunction "73_73") (pintype "passive"))
      (node (ref "J20") (pin "77") (pinfunction "77_77") (pintype "passive"))
      (node (ref "J20") (pin "78") (pinfunction "78_78") (pintype "passive"))
      (node (ref "J20") (pin "81") (pinfunction "81_81") (pintype "passive"))
      (node (ref "J20") (pin "82") (pinfunction "82_82") (pintype "passive"))
      (node (ref "J20") (pin "85") (pinfunction "85_85") (pintype "passive"))
      (node (ref "J20") (pin "86") (pinfunction "86_86") (pintype "passive"))
      (node (ref "J20") (pin "89") (pinfunction "89_89") (pintype "passive"))
      (node (ref "J20") (pin "9") (pinfunction "9_9") (pintype "passive"))
      (node (ref "J20") (pin "90") (pinfunction "90_90") (pintype "passive"))
      (node (ref "J20") (pin "93") (pinfunction "93_93") (pintype "passive"))
      (node (ref "J20") (pin "94") (pinfunction "94_94") (pintype "passive"))
      (node (ref "J20") (pin "98") (pinfunction "98_98") (pintype "passive"))
      (node (ref "J20") (pin "99") (pinfunction "99_99") (pintype "passive"))
      (node (ref "J20") (pin "MP1") (pinfunction "MP1_MP1") (pintype "passive"))
      (node (ref "J20") (pin "MP2") (pinfunction "MP2_MP2") (pintype "passive"))
      (node (ref "R233") (pin "1") (pinfunction "1_1") (pintype "passive"))
      (node (ref "R235") (pin "1") (pinfunction "1_1") (pintype "passive"))
      (node (ref "R236") (pin "1") (pinfunction "1_1") (pintype "passive"))
    )
    (net (code "151") (name "IO_2V5") (class "Default")
      (node (ref "J20") (pin "255") (pinfunction "255_255") (pintype "passive"))
      (node (ref "J20") (pin "257") (pinfunction "257_257") (pintype "passive"))
      (node (ref "J20") (pin "259") (pinfunction "259_259") (pintype "passive"))
      (node (ref "R232") (pin "1") (pinfunction "1_1") (pintype "passive"))
    )
    (net (code "152") (name "Net-(C295-Pad1)") (class "Default")
      (node (ref "C295") (pin "1") (pinfunction "1_1") (pintype "passive"))
      (node (ref "J20") (pin "164") (pinfunction "164_164") (pintype "passive"))
      (node (ref "R232") (pin "2") (pinfunction "2_2") (pintype "passive"))
      (node (ref "R233") (pin "2") (pinfunction "2_2") (pintype "passive"))
    )
    (net (code "153") (name "Net-(C296-Pad1)") (class "Default")
      (node (ref "C296") (pin "1") (pinfunction "1_1") (pintype "passive"))
      (node (ref "J20") (pin "258") (pinfunction "258_258") (pintype "passive"))
      (node (ref "R234") (pin "2") (pinfunction "2_2") (pintype "passive"))
      (node (ref "R235") (pin "2") (pinfunction "2_2") (pintype "passive"))
    )
    (net (code "154") (name "VDD_DDR") (class "Default")
      (node (ref "C290") (pin "1") (pinfunction "1_1") (pintype "passive"))
      (node (ref "C291") (pin "1") (pinfunction "1_1") (pintype "passive"))
      (node (ref "C292") (pin "1") (pinfunction "1_1") (pintype "passive"))
      (node (ref "C293") (pin "1") (pinfunction "1_1") (pintype "passive"))
      (node (ref "C294") (pin "1") (pinfunction "1_1") (pintype "passive"))
      (node (ref "J20") (pin "111") (pinfunction "111_111") (pintype "passive"))
      (node (ref "J20") (pin "112") (pinfunction "112_112") (pintype "passive"))
      (node (ref "J20") (pin "117") (pinfunction "117_117") (pintype "passive"))
      (node (ref "J20") (pin "118") (pinfunction "118_118") (pintype "passive"))
      (node (ref "J20") (pin "123") (pinfunction "123_123") (pintype "passive"))
      (node (ref "J20") (pin "124") (pinfunction "124_124") (pintype "passive"))
      (node (ref "J20") (pin "129") (pinfunction "129_129") (pintype "passive"))
      (node (ref "J20") (pin "130") (pinfunction "130_130") (pintype "passive"))
      (node (ref "J20") (pin "135") (pinfunction "135_135") (pintype "passive"))
      (node (ref "J20") (pin "136") (pinfunction "136_136") (pintype "passive"))
      (node (ref "J20") (pin "141") (pinfunction "141_141") (pintype "passive"))
      (node (ref "J20") (pin "142") (pinfunction "142_142") (pintype "passive"))
      (node (ref "J20") (pin "147") (pinfunction "147_147") (pintype "passive"))
      (node (ref "J20") (pin "148") (pinfunction "148_148") (pintype "passive"))
      (node (ref "J20") (pin "153") (pinfunction "153_153") (pintype "passive"))
      (node (ref "J20") (pin "154") (pinfunction "154_154") (pintype "passive"))
      (node (ref "J20") (pin "159") (pinfunction "159_159") (pintype "passive"))
      (node (ref "J20") (pin "160") (pinfunction "160_160") (pintype "passive"))
      (node (ref "J20") (pin "163") (pinfunction "163_163") (pintype "passive"))
      (node (ref "R234") (pin "1") (pinfunction "1_1") (pintype "passive"))
    )
    (net (code "155") (name "unconnected-(J20-Pad87)") (class "Default")
      (node (ref "J20") (pin "87") (pinfunction "87_87") (pintype "passive"))
    )
    (net (code "156") (name "unconnected-(J20-Pad88)") (class "Default")
      (node (ref "J20") (pin "88") (pinfunction "88_88") (pintype "passive"))
    )
    (net (code "157") (name "unconnected-(J20-Pad91)") (class "Default")
      (node (ref "J20") (pin "91") (pinfunction "91_91") (pintype "passive"))
    )
    (net (code "158") (name "unconnected-(J20-Pad92)") (class "Default")
      (node (ref "J20") (pin "92") (pinfunction "92_92") (pintype "passive"))
    )
    (net (code "159") (name "unconnected-(J20-Pad95)") (class "Default")
      (node (ref "J20") (pin "95") (pinfunction "95_95") (pintype "passive"))
    )
    (net (code "160") (name "unconnected-(J20-Pad96)") (class "Default")
      (node (ref "J20") (pin "96") (pinfunction "96_96") (pintype "passive"))
    )
    (net (code "161") (name "unconnected-(J20-Pad97)") (class "Default")
      (node (ref "J20") (pin "97") (pinfunction "97_97") (pintype "passive"))
    )
    (net (code "162") (name "unconnected-(J20-Pad100)") (class "Default")
      (node (ref "J20") (pin "100") (pinfunction "100_100") (pintype "passive"))
    )
    (net (code "163") (name "unconnected-(J20-Pad101)") (class "Default")
      (node (ref "J20") (pin "101") (pinfunction "101_101") (pintype "passive"))
    )
    (net (code "164") (name "unconnected-(J20-Pad104)") (class "Default")
      (node (ref "J20") (pin "104") (pinfunction "104_104") (pintype "passive"))
    )
    (net (code "165") (name "unconnected-(J20-Pad105)") (class "Default")
      (node (ref "J20") (pin "105") (pinfunction "105_105") (pintype "passive"))
    )
    (net (code "166") (name "unconnected-(J20-Pad110)") (class "Default")
      (node (ref "J20") (pin "110") (pinfunction "110_110") (pintype "passive"))
    )
    (net (code "167") (name "unconnected-(J20-Pad134)") (class "Default")
      (node (ref "J20") (pin "134") (pinfunction "134_134") (pintype "passive"))
    )
    (net (code "168") (name "unconnected-(J20-Pad157)") (class "Default")
      (node (ref "J20") (pin "157") (pinfunction "157_157") (pintype "passive"))
    )
    (net (code "169") (name "unconnected-(J20-Pad161)") (class "Default")
      (node (ref "J20") (pin "161") (pinfunction "161_161") (pintype "passive"))
    )
    (net (code "170") (name "unconnected-(J20-Pad162)") (class "Default")
      (node (ref "J20") (pin "162") (pinfunction "162_162") (pintype "passive"))
    )
    (net (code "171") (name "unconnected-(J20-Pad165)") (class "Default")
      (node (ref "J20") (pin "165") (pinfunction "165_165") (pintype "passive"))
    )
  )
)
